# p1_control_block.net
KiCad netlist of a schematic drawn in Altium Designer
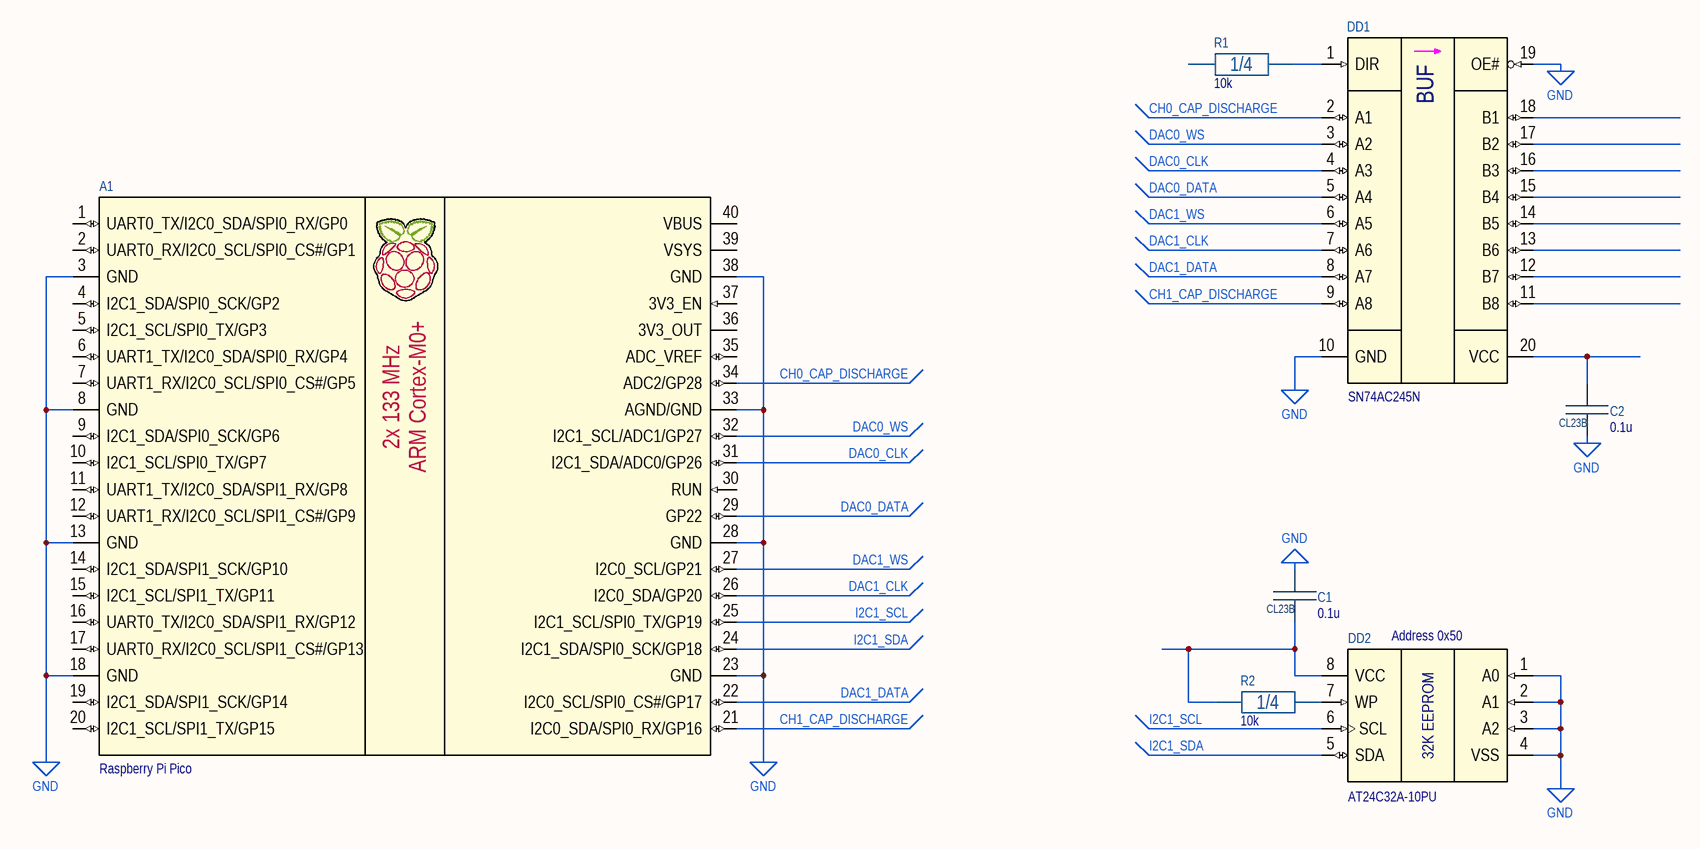
[diagram p0: p1_control_block.SchDoc]

(export (version "E")
  (design (tool "Eeschema 10.0.6"))
  (components
    (comp (ref "A1")
      (value "Raspberry Pi Pico")
      (footprint "PcbLib_Others:Raspberry_Pi_Pico")
      (description "Board Raspberry Pi Pico")
      (fields (field (name "MANUFACTURER") "Raspberry Pi"))
      (libsource (lib "Schlib_RaspberryPi") (part "Raspberry Pi Pico"))
    )
    (comp (ref "C1")
      (value "0.1u")
      (footprint "PcbLib_RC:CL23B_7.2x2.5")
      (description "Box-type metallized polyester film capacitor")
      (fields
        (field (name "TOLERANCE") "± * %")
        (field (name "VOLTAGE") "63V")
        (field (name "PACKAGE") "CL23B")
      )
      (libsource (lib "Schlib_RC") (part "CL23B"))
    )
    (comp (ref "C2")
      (value "0.1u")
      (footprint "PcbLib_RC:CL23B_7.2x2.5")
      (description "Box-type metallized polyester film capacitor")
      (fields
        (field (name "TOLERANCE") "± * %")
        (field (name "VOLTAGE") "63V")
        (field (name "PACKAGE") "CL23B")
      )
      (libsource (lib "Schlib_RC") (part "CL23B"))
    )
    (comp (ref "DD1")
      (value "SN74AC245N")
      (footprint "PcbLib_ICs:DIP-20P-M01")
      (description "8-bit Bus Transceiver with 3-state outputs")
      (fields (field (name "MANUFACTURER") "Texas Instruments"))
      (libsource (lib "Schlib_Texas_Instruments") (part "SN74AC245N"))
    )
    (comp (ref "DD2")
      (value "AT24C32A-10PU")
      (footprint "PcbLib_ICs:DIP-8P-M01_with_SO8")
      (description "32K I2C Serial EEPROM")
      (fields (field (name "MANUFACTURER") "Microchip Technology"))
      (libsource (lib "Schlib_Microchip") (part "AT24C32A-10PU"))
    )
    (comp (ref "R1")
      (value "10k")
      (footprint "PcbLib_RC:CFR-25")
      (description "Resistor 1/4W")
      (fields
        (field (name "TOLERANCE") "± 1 %")
        (field (name "PART NUMBER") "MFR-25FTF52-10K")
        (field (name "PACKAGE") "1/4")
      )
      (libsource (lib "Schlib_RC") (part "CF25"))
    )
    (comp (ref "R2")
      (value "10k")
      (footprint "PcbLib_RC:CFR-25")
      (description "Resistor 1/4W")
      (fields
        (field (name "TOLERANCE") "± 1 %")
        (field (name "PART NUMBER") "MFR-25FTF52-10K")
        (field (name "PACKAGE") "1/4")
      )
      (libsource (lib "Schlib_RC") (part "CF25"))
    )
  )
  (nets
    (net (code "1") (name "/CH0_CAP_DISCHARGE") (class "Default")
      (node (ref "A1") (pin "34") (pinfunction "ADC2/GP28_34") (pintype "bidirectional"))
      (node (ref "DD1") (pin "2") (pinfunction "A1_2") (pintype "bidirectional"))
    )
    (net (code "2") (name "/CH1_CAP_DISCHARGE") (class "Default")
      (node (ref "A1") (pin "21") (pinfunction "I2C0_SDA/SPI0_RX/GP16_21") (pintype "bidirectional"))
      (node (ref "DD1") (pin "9") (pinfunction "A8_9") (pintype "bidirectional"))
    )
    (net (code "3") (name "/DAC0_CLK") (class "Default")
      (node (ref "A1") (pin "31") (pinfunction "I2C1_SDA/ADC0/GP26_31") (pintype "bidirectional"))
      (node (ref "DD1") (pin "4") (pinfunction "A3_4") (pintype "bidirectional"))
    )
    (net (code "4") (name "/DAC0_DATA") (class "Default")
      (node (ref "A1") (pin "29") (pinfunction "GP22_29") (pintype "bidirectional"))
      (node (ref "DD1") (pin "5") (pinfunction "A4_5") (pintype "bidirectional"))
    )
    (net (code "5") (name "/DAC0_WS") (class "Default")
      (node (ref "A1") (pin "32") (pinfunction "I2C1_SCL/ADC1/GP27_32") (pintype "bidirectional"))
      (node (ref "DD1") (pin "3") (pinfunction "A2_3") (pintype "bidirectional"))
    )
    (net (code "6") (name "/DAC1_CLK") (class "Default")
      (node (ref "A1") (pin "26") (pinfunction "I2C0_SDA/GP20_26") (pintype "bidirectional"))
      (node (ref "DD1") (pin "7") (pinfunction "A6_7") (pintype "bidirectional"))
    )
    (net (code "7") (name "/DAC1_DATA") (class "Default")
      (node (ref "A1") (pin "22") (pinfunction "I2C0_SCL/SPI0_CS#/GP17_22") (pintype "bidirectional"))
      (node (ref "DD1") (pin "8") (pinfunction "A7_8") (pintype "bidirectional"))
    )
    (net (code "8") (name "/DAC1_WS") (class "Default")
      (node (ref "A1") (pin "27") (pinfunction "I2C0_SCL/GP21_27") (pintype "bidirectional"))
      (node (ref "DD1") (pin "6") (pinfunction "A5_6") (pintype "bidirectional"))
    )
    (net (code "9") (name "/I2C1_SCL") (class "Default")
      (node (ref "A1") (pin "25") (pinfunction "I2C1_SCL/SPI0_TX/GP19_25") (pintype "bidirectional"))
      (node (ref "DD2") (pin "6") (pinfunction "SCL_6") (pintype "input"))
    )
    (net (code "10") (name "/I2C1_SDA") (class "Default")
      (node (ref "A1") (pin "24") (pinfunction "I2C1_SDA/SPI0_SCK/GP18_24") (pintype "bidirectional"))
      (node (ref "DD2") (pin "5") (pinfunction "SDA_5") (pintype "bidirectional"))
    )
    (net (code "11") (name "GND") (class "Default")
      (node (ref "A1") (pin "13") (pinfunction "GND_13") (pintype "power_in"))
      (node (ref "A1") (pin "18") (pinfunction "GND_18") (pintype "power_in"))
      (node (ref "A1") (pin "23") (pinfunction "GND_23") (pintype "power_in"))
      (node (ref "A1") (pin "28") (pinfunction "GND_28") (pintype "power_in"))
      (node (ref "A1") (pin "3") (pinfunction "GND_3") (pintype "power_in"))
      (node (ref "A1") (pin "33") (pinfunction "AGND/GND_33") (pintype "power_in"))
      (node (ref "A1") (pin "38") (pinfunction "GND_38") (pintype "power_in"))
      (node (ref "A1") (pin "8") (pinfunction "GND_8") (pintype "power_in"))
      (node (ref "C1") (pin "1") (pinfunction "1_1") (pintype "passive"))
      (node (ref "C2") (pin "2") (pinfunction "2_2") (pintype "passive"))
      (node (ref "DD1") (pin "10") (pinfunction "GND_10") (pintype "power_in"))
      (node (ref "DD1") (pin "19") (pinfunction "OE#_19") (pintype "input"))
      (node (ref "DD2") (pin "1") (pinfunction "A0_1") (pintype "input"))
      (node (ref "DD2") (pin "2") (pinfunction "A1_2") (pintype "input"))
      (node (ref "DD2") (pin "3") (pinfunction "A2_3") (pintype "input"))
      (node (ref "DD2") (pin "4") (pinfunction "VSS_4") (pintype "power_in"))
    )
    (net (code "12") (name "Net-(DD1-DIR)") (class "Default")
      (node (ref "DD1") (pin "1") (pinfunction "DIR_1") (pintype "input"))
      (node (ref "R1") (pin "2") (pinfunction "2_2") (pintype "passive"))
    )
    (net (code "13") (name "Net-(DD1-VCC)") (class "Default")
      (node (ref "C2") (pin "1") (pinfunction "1_1") (pintype "passive"))
      (node (ref "DD1") (pin "20") (pinfunction "VCC_20") (pintype "power_in"))
    )
    (net (code "14") (name "Net-(DD2-VCC)") (class "Default")
      (node (ref "C1") (pin "2") (pinfunction "2_2") (pintype "passive"))
      (node (ref "DD2") (pin "8") (pinfunction "VCC_8") (pintype "power_in"))
      (node (ref "R2") (pin "1") (pinfunction "1_1") (pintype "passive"))
    )
    (net (code "15") (name "Net-(DD2-WP)") (class "Default")
      (node (ref "DD2") (pin "7") (pinfunction "WP_7") (pintype "input"))
      (node (ref "R2") (pin "2") (pinfunction "2_2") (pintype "passive"))
    )
    (net (code "16") (name "unconnected-(A1-3V3_EN-Pad37)") (class "Default")
      (node (ref "A1") (pin "37") (pinfunction "3V3_EN_37") (pintype "input"))
    )
    (net (code "17") (name "unconnected-(A1-3V3_OUT-Pad36)") (class "Default")
      (node (ref "A1") (pin "36") (pinfunction "3V3_OUT_36") (pintype "power_in"))
    )
    (net (code "18") (name "unconnected-(A1-ADC_VREF-Pad35)") (class "Default")
      (node (ref "A1") (pin "35") (pinfunction "ADC_VREF_35") (pintype "bidirectional"))
    )
    (net (code "19") (name "unconnected-(A1-I2C1_SCL{slash}SPI0_TX{slash}GP3-Pad5)") (class "Default")
      (node (ref "A1") (pin "5") (pinfunction "I2C1_SCL/SPI0_TX/GP3_5") (pintype "bidirectional"))
    )
    (net (code "20") (name "unconnected-(A1-I2C1_SCL{slash}SPI0_TX{slash}GP7-Pad10)") (class "Default")
      (node (ref "A1") (pin "10") (pinfunction "I2C1_SCL/SPI0_TX/GP7_10") (pintype "bidirectional"))
    )
    (net (code "21") (name "unconnected-(A1-I2C1_SCL{slash}SPI1_TX{slash}GP11-Pad15)") (class "Default")
      (node (ref "A1") (pin "15") (pinfunction "I2C1_SCL/SPI1_TX/GP11_15") (pintype "bidirectional"))
    )
    (net (code "22") (name "unconnected-(A1-I2C1_SCL{slash}SPI1_TX{slash}GP15-Pad20)") (class "Default")
      (node (ref "A1") (pin "20") (pinfunction "I2C1_SCL/SPI1_TX/GP15_20") (pintype "bidirectional"))
    )
    (net (code "23") (name "unconnected-(A1-I2C1_SDA{slash}SPI0_SCK{slash}GP2-Pad4)") (class "Default")
      (node (ref "A1") (pin "4") (pinfunction "I2C1_SDA/SPI0_SCK/GP2_4") (pintype "bidirectional"))
    )
    (net (code "24") (name "unconnected-(A1-I2C1_SDA{slash}SPI0_SCK{slash}GP6-Pad9)") (class "Default")
      (node (ref "A1") (pin "9") (pinfunction "I2C1_SDA/SPI0_SCK/GP6_9") (pintype "bidirectional"))
    )
    (net (code "25") (name "unconnected-(A1-I2C1_SDA{slash}SPI1_SCK{slash}GP10-Pad14)") (class "Default")
      (node (ref "A1") (pin "14") (pinfunction "I2C1_SDA/SPI1_SCK/GP10_14") (pintype "bidirectional"))
    )
    (net (code "26") (name "unconnected-(A1-I2C1_SDA{slash}SPI1_SCK{slash}GP14-Pad19)") (class "Default")
      (node (ref "A1") (pin "19") (pinfunction "I2C1_SDA/SPI1_SCK/GP14_19") (pintype "bidirectional"))
    )
    (net (code "27") (name "unconnected-(A1-RUN-Pad30)") (class "Default")
      (node (ref "A1") (pin "30") (pinfunction "RUN_30") (pintype "input"))
    )
    (net (code "28") (name "unconnected-(A1-UART0_RX{slash}I2C0_SCL{slash}SPI0_CS#{slash}GP1-Pad2)") (class "Default")
      (node (ref "A1") (pin "2") (pinfunction "UART0_RX/I2C0_SCL/SPI0_CS#/GP1_2") (pintype "bidirectional"))
    )
    (net (code "29") (name "unconnected-(A1-UART0_RX{slash}I2C0_SCL{slash}SPI1_CS#{slash}GP13-Pad17)") (class "Default")
      (node (ref "A1") (pin "17") (pinfunction "UART0_RX/I2C0_SCL/SPI1_CS#/GP13_17") (pintype "bidirectional"))
    )
    (net (code "30") (name "unconnected-(A1-UART0_TX{slash}I2C0_SDA{slash}SPI0_RX{slash}GP0-Pad1)") (class "Default")
      (node (ref "A1") (pin "1") (pinfunction "UART0_TX/I2C0_SDA/SPI0_RX/GP0_1") (pintype "bidirectional"))
    )
    (net (code "31") (name "unconnected-(A1-UART0_TX{slash}I2C0_SDA{slash}SPI1_RX{slash}GP12-Pad16)") (class "Default")
      (node (ref "A1") (pin "16") (pinfunction "UART0_TX/I2C0_SDA/SPI1_RX/GP12_16") (pintype "bidirectional"))
    )
    (net (code "32") (name "unconnected-(A1-UART1_RX{slash}I2C0_SCL{slash}SPI0_CS#{slash}GP5-Pad7)") (class "Default")
      (node (ref "A1") (pin "7") (pinfunction "UART1_RX/I2C0_SCL/SPI0_CS#/GP5_7") (pintype "bidirectional"))
    )
    (net (code "33") (name "unconnected-(A1-UART1_RX{slash}I2C0_SCL{slash}SPI1_CS#{slash}GP9-Pad12)") (class "Default")
      (node (ref "A1") (pin "12") (pinfunction "UART1_RX/I2C0_SCL/SPI1_CS#/GP9_12") (pintype "bidirectional"))
    )
    (net (code "34") (name "unconnected-(A1-UART1_TX{slash}I2C0_SDA{slash}SPI0_RX{slash}GP4-Pad6)") (class "Default")
      (node (ref "A1") (pin "6") (pinfunction "UART1_TX/I2C0_SDA/SPI0_RX/GP4_6") (pintype "bidirectional"))
    )
    (net (code "35") (name "unconnected-(A1-UART1_TX{slash}I2C0_SDA{slash}SPI1_RX{slash}GP8-Pad11)") (class "Default")
      (node (ref "A1") (pin "11") (pinfunction "UART1_TX/I2C0_SDA/SPI1_RX/GP8_11") (pintype "bidirectional"))
    )
    (net (code "36") (name "unconnected-(A1-VBUS-Pad40)") (class "Default")
      (node (ref "A1") (pin "40") (pinfunction "VBUS_40") (pintype "power_in"))
    )
    (net (code "37") (name "unconnected-(A1-VSYS-Pad39)") (class "Default")
      (node (ref "A1") (pin "39") (pinfunction "VSYS_39") (pintype "power_in"))
    )
    (net (code "38") (name "unconnected-(DD1-B1-Pad18)") (class "Default")
      (node (ref "DD1") (pin "18") (pinfunction "B1_18") (pintype "bidirectional"))
    )
    (net (code "39") (name "unconnected-(DD1-B2-Pad17)") (class "Default")
      (node (ref "DD1") (pin "17") (pinfunction "B2_17") (pintype "bidirectional"))
    )
    (net (code "40") (name "unconnected-(DD1-B3-Pad16)") (class "Default")
      (node (ref "DD1") (pin "16") (pinfunction "B3_16") (pintype "bidirectional"))
    )
    (net (code "41") (name "unconnected-(DD1-B4-Pad15)") (class "Default")
      (node (ref "DD1") (pin "15") (pinfunction "B4_15") (pintype "bidirectional"))
    )
    (net (code "42") (name "unconnected-(DD1-B5-Pad14)") (class "Default")
      (node (ref "DD1") (pin "14") (pinfunction "B5_14") (pintype "bidirectional"))
    )
    (net (code "43") (name "unconnected-(DD1-B6-Pad13)") (class "Default")
      (node (ref "DD1") (pin "13") (pinfunction "B6_13") (pintype "bidirectional"))
    )
    (net (code "44") (name "unconnected-(DD1-B7-Pad12)") (class "Default")
      (node (ref "DD1") (pin "12") (pinfunction "B7_12") (pintype "bidirectional"))
    )
    (net (code "45") (name "unconnected-(DD1-B8-Pad11)") (class "Default")
      (node (ref "DD1") (pin "11") (pinfunction "B8_11") (pintype "bidirectional"))
    )
    (net (code "46") (name "unconnected-(R1-Pad1)") (class "Default")
      (node (ref "R1") (pin "1") (pinfunction "1_1") (pintype "passive"))
    )
  )
)
